# brewpi.net
KiCad netlist of a schematic drawn in EAGLE
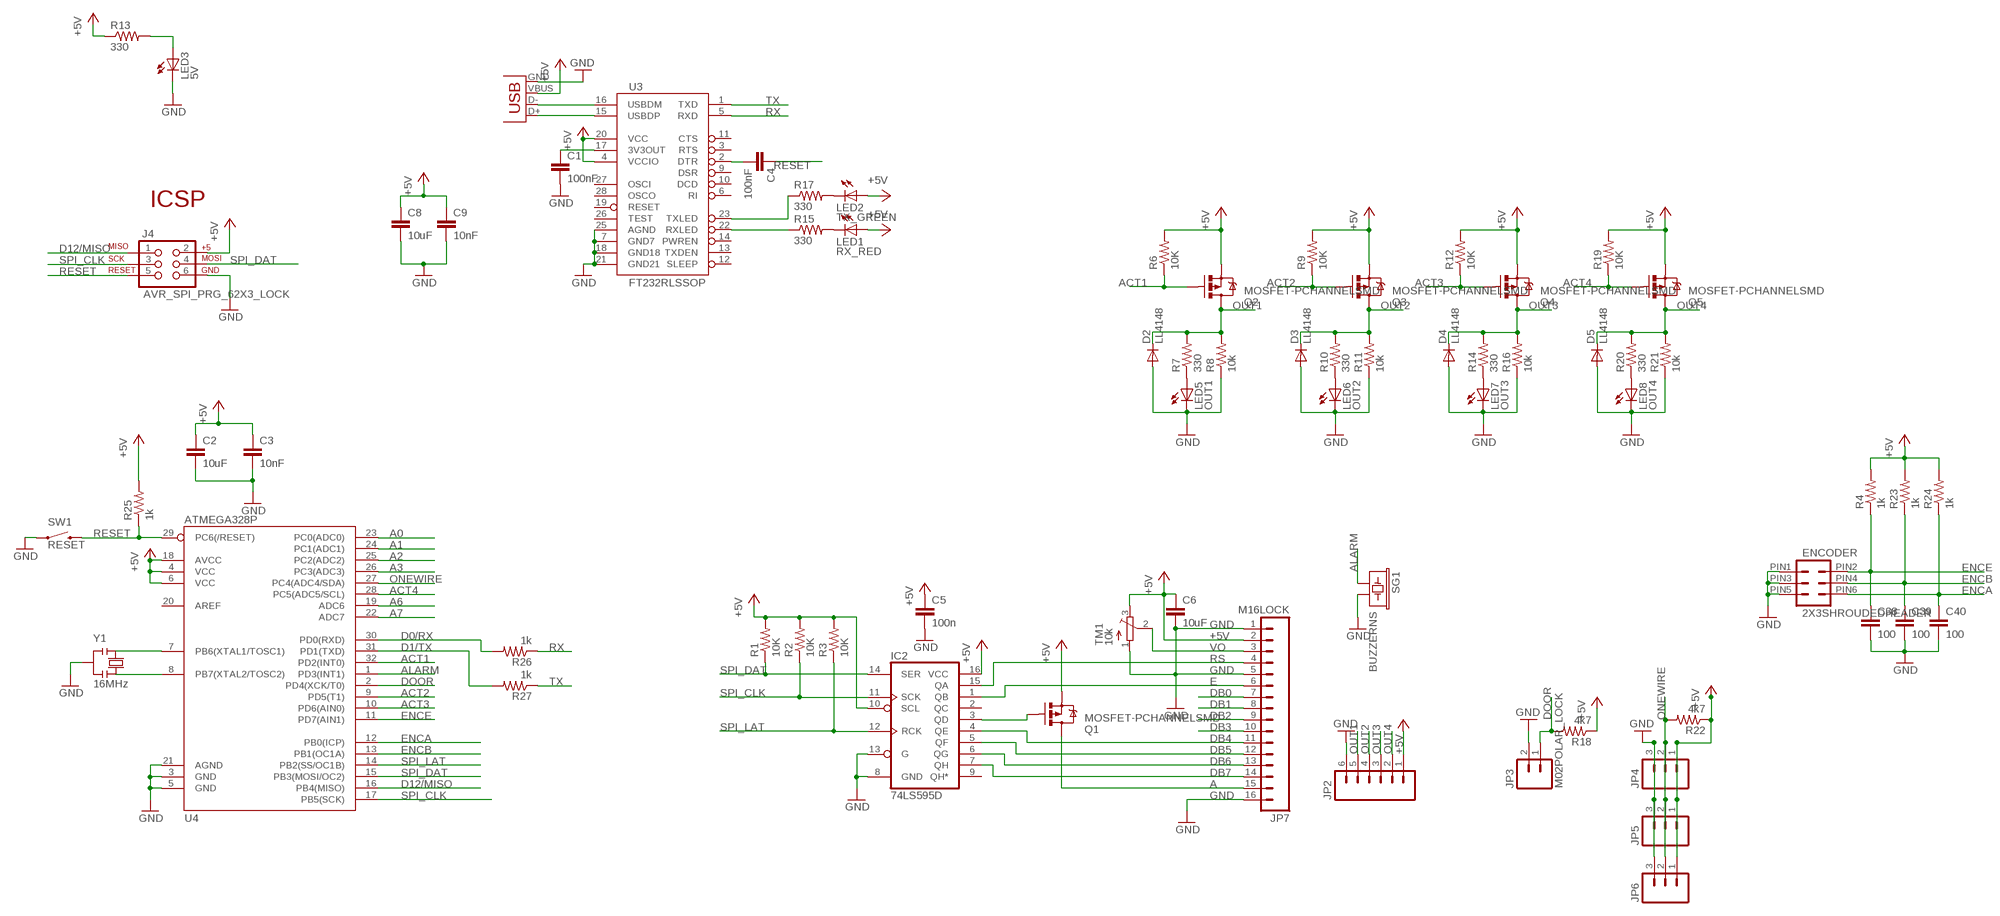
[diagram p0: schematic, sheet 1]

(export (version "E")
  (design (tool "Eeschema 10.0.6"))
  (components
    (comp (ref "C1")
      (value "100nF")
      (footprint "eagle-import:0603-CAP")
      (libsource (lib "eagle-import") (part "SparkFun-Capacitors_CAP0603-CAP"))
    )
    (comp (ref "C2")
      (value "10uF")
      (footprint "eagle-import:0603-CAP")
      (libsource (lib "eagle-import") (part "SparkFun-Capacitors_CAP0603-CAP"))
    )
    (comp (ref "C3")
      (value "10nF")
      (footprint "eagle-import:0603-CAP")
      (libsource (lib "eagle-import") (part "SparkFun-Capacitors_CAP0603-CAP"))
    )
    (comp (ref "C4")
      (value "100nF")
      (footprint "eagle-import:0603-CAP")
      (libsource (lib "eagle-import") (part "SparkFun-Capacitors_CAP0603-CAP"))
    )
    (comp (ref "C5")
      (value "100n")
      (footprint "eagle-import:0603-CAP")
      (libsource (lib "eagle-import") (part "SparkFun-Capacitors_CAP0603-CAP"))
    )
    (comp (ref "C6")
      (value "10uF")
      (footprint "eagle-import:0603-CAP")
      (libsource (lib "eagle-import") (part "SparkFun-Capacitors_CAP0603-CAP"))
    )
    (comp (ref "C8")
      (value "10uF")
      (footprint "eagle-import:0603-CAP")
      (libsource (lib "eagle-import") (part "SparkFun-Capacitors_CAP0603-CAP"))
    )
    (comp (ref "C9")
      (value "10nF")
      (footprint "eagle-import:0603-CAP")
      (libsource (lib "eagle-import") (part "SparkFun-Capacitors_CAP0603-CAP"))
    )
    (comp (ref "C38")
      (value "100")
      (footprint "eagle-import:0603-CAP")
      (libsource (lib "eagle-import") (part "CAP0603-CAP"))
    )
    (comp (ref "C39")
      (value "100")
      (footprint "eagle-import:0603-CAP")
      (libsource (lib "eagle-import") (part "CAP0603-CAP"))
    )
    (comp (ref "C40")
      (value "100")
      (footprint "eagle-import:0603-CAP")
      (libsource (lib "eagle-import") (part "CAP0603-CAP"))
    )
    (comp (ref "D2")
      (value "LL4148")
      (footprint "eagle-import:MLL34")
      (libsource (lib "eagle-import") (part "LL4148"))
    )
    (comp (ref "D3")
      (value "LL4148")
      (footprint "eagle-import:MLL34")
      (libsource (lib "eagle-import") (part "LL4148"))
    )
    (comp (ref "D4")
      (value "LL4148")
      (footprint "eagle-import:MLL34")
      (libsource (lib "eagle-import") (part "LL4148"))
    )
    (comp (ref "D5")
      (value "LL4148")
      (footprint "eagle-import:MLL34")
      (libsource (lib "eagle-import") (part "LL4148"))
    )
    (comp (ref "ENCODER")
      (value "2X3SHROUDEDHEADER")
      (footprint "eagle-import:2X3SHROUDEDHEADER")
      (libsource (lib "eagle-import") (part "2X3SHROUDEDHEADER"))
    )
    (comp (ref "IC2")
      (value "74LS595D")
      (footprint "eagle-import:SO16")
      (libsource (lib "eagle-import") (part "74595DLS"))
    )
    (comp (ref "J4")
      (value "AVR_SPI_PRG_62X3_LOCK")
      (footprint "eagle-import:2X3_LOCK")
      (libsource (lib "eagle-import") (part "AVR_SPI_PRG_62X3_LOCK"))
    )
    (comp (ref "JP1")
      (value "USBSMD")
      (footprint "eagle-import:USB-MINIB")
      (libsource (lib "eagle-import") (part "USBSMD"))
    )
    (comp (ref "JP2")
      (value "M06POLAR_LOCK")
      (footprint "eagle-import:MOLEX-1X6_LOCK")
      (libsource (lib "eagle-import") (part "M06POLAR_LOCK"))
    )
    (comp (ref "JP3")
      (value "M02POLAR_LOCK")
      (footprint "eagle-import:MOLEX-1X2_LOCK")
      (libsource (lib "eagle-import") (part "M02POLAR_LOCK"))
    )
    (comp (ref "JP4")
      (value "M03POLAR_LOCK")
      (footprint "eagle-import:MOLEX-1X3_LOCK")
      (libsource (lib "eagle-import") (part "M03POLAR_LOCK"))
    )
    (comp (ref "JP5")
      (value "M03POLAR_LOCK")
      (footprint "eagle-import:MOLEX-1X3_LOCK")
      (libsource (lib "eagle-import") (part "M03POLAR_LOCK"))
    )
    (comp (ref "JP6")
      (value "M03POLAR_LOCK")
      (footprint "eagle-import:MOLEX-1X3_LOCK")
      (libsource (lib "eagle-import") (part "M03POLAR_LOCK"))
    )
    (comp (ref "JP7")
      (value "M16LOCK")
      (footprint "eagle-import:1X16_LOCK")
      (libsource (lib "eagle-import") (part "M16LOCK"))
    )
    (comp (ref "LED1")
      (value "RX_RED")
      (footprint "eagle-import:LED-0603")
      (libsource (lib "eagle-import") (part "LED0603"))
    )
    (comp (ref "LED2")
      (value "TX_GREEN")
      (footprint "eagle-import:LED-0603")
      (libsource (lib "eagle-import") (part "LED0603"))
    )
    (comp (ref "LED3")
      (value "5V")
      (footprint "eagle-import:LED-0603")
      (libsource (lib "eagle-import") (part "LED0603"))
    )
    (comp (ref "LED5")
      (value "OUT1")
      (footprint "eagle-import:LED-0603")
      (libsource (lib "eagle-import") (part "LED0603"))
    )
    (comp (ref "LED6")
      (value "OUT2")
      (footprint "eagle-import:LED-0603")
      (libsource (lib "eagle-import") (part "LED0603"))
    )
    (comp (ref "LED7")
      (value "OUT3")
      (footprint "eagle-import:LED-0603")
      (libsource (lib "eagle-import") (part "LED0603"))
    )
    (comp (ref "LED8")
      (value "OUT4")
      (footprint "eagle-import:LED-0603")
      (libsource (lib "eagle-import") (part "LED0603"))
    )
    (comp (ref "Q1")
      (value "MOSFET-PCHANNELSMD")
      (footprint "eagle-import:SOT23-3")
      (libsource (lib "eagle-import") (part "MOSFET-PCHANNELSMD"))
    )
    (comp (ref "Q2")
      (value "MOSFET-PCHANNELSMD")
      (footprint "eagle-import:SOT23-3")
      (libsource (lib "eagle-import") (part "MOSFET-PCHANNELSMD"))
    )
    (comp (ref "Q3")
      (value "MOSFET-PCHANNELSMD")
      (footprint "eagle-import:SOT23-3")
      (libsource (lib "eagle-import") (part "MOSFET-PCHANNELSMD"))
    )
    (comp (ref "Q4")
      (value "MOSFET-PCHANNELSMD")
      (footprint "eagle-import:SOT23-3")
      (libsource (lib "eagle-import") (part "MOSFET-PCHANNELSMD"))
    )
    (comp (ref "Q5")
      (value "MOSFET-PCHANNELSMD")
      (footprint "eagle-import:SOT23-3")
      (libsource (lib "eagle-import") (part "MOSFET-PCHANNELSMD"))
    )
    (comp (ref "R1")
      (value "10K")
      (footprint "eagle-import:0603-RES")
      (libsource (lib "eagle-import") (part "RESISTOR0603-RES"))
    )
    (comp (ref "R2")
      (value "10K")
      (footprint "eagle-import:0603-RES")
      (libsource (lib "eagle-import") (part "RESISTOR0603-RES"))
    )
    (comp (ref "R3")
      (value "10K")
      (footprint "eagle-import:0603-RES")
      (libsource (lib "eagle-import") (part "RESISTOR0603-RES"))
    )
    (comp (ref "R4")
      (value "1k")
      (footprint "eagle-import:R0603")
      (libsource (lib "eagle-import") (part "R-US_R0603"))
    )
    (comp (ref "R6")
      (value "10K")
      (footprint "eagle-import:0603-RES")
      (libsource (lib "eagle-import") (part "RESISTOR0603-RES"))
    )
    (comp (ref "R7")
      (value "330")
      (footprint "eagle-import:0603-RES")
      (libsource (lib "eagle-import") (part "RESISTOR0603-RES"))
    )
    (comp (ref "R8")
      (value "10k")
      (footprint "eagle-import:0603-RES")
      (libsource (lib "eagle-import") (part "RESISTOR0603-RES"))
    )
    (comp (ref "R9")
      (value "10K")
      (footprint "eagle-import:0603-RES")
      (libsource (lib "eagle-import") (part "RESISTOR0603-RES"))
    )
    (comp (ref "R10")
      (value "330")
      (footprint "eagle-import:0603-RES")
      (libsource (lib "eagle-import") (part "RESISTOR0603-RES"))
    )
    (comp (ref "R11")
      (value "10k")
      (footprint "eagle-import:0603-RES")
      (libsource (lib "eagle-import") (part "RESISTOR0603-RES"))
    )
    (comp (ref "R12")
      (value "10K")
      (footprint "eagle-import:0603-RES")
      (libsource (lib "eagle-import") (part "RESISTOR0603-RES"))
    )
    (comp (ref "R13")
      (value "330")
      (footprint "eagle-import:0603-RES")
      (libsource (lib "eagle-import") (part "RESISTOR0603"))
    )
    (comp (ref "R14")
      (value "330")
      (footprint "eagle-import:0603-RES")
      (libsource (lib "eagle-import") (part "RESISTOR0603-RES"))
    )
    (comp (ref "R15")
      (value "330")
      (footprint "eagle-import:0603-RES")
      (libsource (lib "eagle-import") (part "RESISTOR0603"))
    )
    (comp (ref "R16")
      (value "10k")
      (footprint "eagle-import:0603-RES")
      (libsource (lib "eagle-import") (part "RESISTOR0603-RES"))
    )
    (comp (ref "R17")
      (value "330")
      (footprint "eagle-import:0603-RES")
      (libsource (lib "eagle-import") (part "RESISTOR0603"))
    )
    (comp (ref "R18")
      (value "4k7")
      (footprint "eagle-import:0603-RES")
      (libsource (lib "eagle-import") (part "RESISTOR0603-RES"))
    )
    (comp (ref "R19")
      (value "10K")
      (footprint "eagle-import:0603-RES")
      (libsource (lib "eagle-import") (part "RESISTOR0603-RES"))
    )
    (comp (ref "R20")
      (value "330")
      (footprint "eagle-import:0603-RES")
      (libsource (lib "eagle-import") (part "RESISTOR0603-RES"))
    )
    (comp (ref "R21")
      (value "10k")
      (footprint "eagle-import:0603-RES")
      (libsource (lib "eagle-import") (part "RESISTOR0603-RES"))
    )
    (comp (ref "R22")
      (value "4k7")
      (footprint "eagle-import:0603-RES")
      (libsource (lib "eagle-import") (part "RESISTOR0603-RES"))
    )
    (comp (ref "R23")
      (value "1k")
      (footprint "eagle-import:R0603")
      (libsource (lib "eagle-import") (part "R-US_R0603"))
    )
    (comp (ref "R24")
      (value "1k")
      (footprint "eagle-import:R0603")
      (libsource (lib "eagle-import") (part "R-US_R0603"))
    )
    (comp (ref "R25")
      (value "1k")
      (footprint "eagle-import:0603-RES")
      (libsource (lib "eagle-import") (part "RESISTOR0603"))
    )
    (comp (ref "R26")
      (value "1k")
      (footprint "eagle-import:0603-RES")
      (libsource (lib "eagle-import") (part "RESISTOR0603"))
    )
    (comp (ref "R27")
      (value "1k")
      (footprint "eagle-import:0603-RES")
      (libsource (lib "eagle-import") (part "RESISTOR0603"))
    )
    (comp (ref "SG1")
      (value "BUZZERNS")
      (footprint "eagle-import:BUZZER-12MM-NS")
      (libsource (lib "eagle-import") (part "BUZZERNS"))
    )
    (comp (ref "SW1")
      (value "RESET")
      (footprint "eagle-import:TACTILE_SWITCH_TALL")
      (libsource (lib "eagle-import") (part "SWITCH-MOMENTARY-2SMD-4"))
    )
    (comp (ref "TM1")
      (value "10k")
      (footprint "eagle-import:TC33X")
      (libsource (lib "eagle-import") (part "TRIMPOTTC33X"))
    )
    (comp (ref "U3")
      (value "FT232RLSSOP")
      (footprint "eagle-import:SSOP28DB")
      (libsource (lib "eagle-import") (part "FT232RLSSOP"))
    )
    (comp (ref "U4")
      (value "ATMEGA328P")
      (footprint "eagle-import:TQFP32-08")
      (libsource (lib "eagle-import") (part "ATMEGA328_SMT"))
    )
    (comp (ref "Y1")
      (value "16MHz")
      (footprint "eagle-import:RESONATOR")
      (libsource (lib "eagle-import") (part "RESONATORMU"))
    )
  )
  (nets
    (net (code "1") (name "+5V") (class "Default")
      (node (ref "C2") (pin "1") (pinfunction "1_1") (pintype "passive"))
      (node (ref "C3") (pin "1") (pinfunction "1_1") (pintype "passive"))
      (node (ref "C5") (pin "1") (pinfunction "1_1") (pintype "passive"))
      (node (ref "C6") (pin "1") (pinfunction "1_1") (pintype "passive"))
      (node (ref "C8") (pin "1") (pinfunction "1_1") (pintype "passive"))
      (node (ref "C9") (pin "1") (pinfunction "1_1") (pintype "passive"))
      (node (ref "IC2") (pin "10") (pinfunction "SCL_10") (pintype "input"))
      (node (ref "IC2") (pin "16") (pinfunction "VCC_16") (pintype "power_in"))
      (node (ref "J4") (pin "2") (pinfunction "2_2") (pintype "passive"))
      (node (ref "JP1") (pin "VBUS") (pinfunction "VBUS_VBUS") (pintype "bidirectional"))
      (node (ref "JP2") (pin "1") (pinfunction "1_1") (pintype "passive"))
      (node (ref "JP4") (pin "1") (pinfunction "1_1") (pintype "passive"))
      (node (ref "JP5") (pin "1") (pinfunction "1_1") (pintype "passive"))
      (node (ref "JP6") (pin "1") (pinfunction "1_1") (pintype "passive"))
      (node (ref "JP7") (pin "2") (pinfunction "2_2") (pintype "passive"))
      (node (ref "LED1") (pin "A") (pinfunction "A_A") (pintype "passive"))
      (node (ref "LED2") (pin "A") (pinfunction "A_A") (pintype "passive"))
      (node (ref "Q1") (pin "2") (pinfunction "S_2") (pintype "passive"))
      (node (ref "Q2") (pin "2") (pinfunction "S_2") (pintype "passive"))
      (node (ref "Q3") (pin "2") (pinfunction "S_2") (pintype "passive"))
      (node (ref "Q4") (pin "2") (pinfunction "S_2") (pintype "passive"))
      (node (ref "Q5") (pin "2") (pinfunction "S_2") (pintype "passive"))
      (node (ref "R1") (pin "2") (pinfunction "2_2") (pintype "passive"))
      (node (ref "R12") (pin "2") (pinfunction "2_2") (pintype "passive"))
      (node (ref "R13") (pin "1") (pinfunction "1_1") (pintype "passive"))
      (node (ref "R18") (pin "1") (pinfunction "1_1") (pintype "passive"))
      (node (ref "R19") (pin "2") (pinfunction "2_2") (pintype "passive"))
      (node (ref "R2") (pin "2") (pinfunction "2_2") (pintype "passive"))
      (node (ref "R22") (pin "1") (pinfunction "1_1") (pintype "passive"))
      (node (ref "R23") (pin "2") (pinfunction "2_2") (pintype "passive"))
      (node (ref "R24") (pin "2") (pinfunction "2_2") (pintype "passive"))
      (node (ref "R25") (pin "2") (pinfunction "2_2") (pintype "passive"))
      (node (ref "R3") (pin "2") (pinfunction "2_2") (pintype "passive"))
      (node (ref "R4") (pin "2") (pinfunction "2_2") (pintype "passive"))
      (node (ref "R6") (pin "2") (pinfunction "2_2") (pintype "passive"))
      (node (ref "R9") (pin "2") (pinfunction "2_2") (pintype "passive"))
      (node (ref "TM1") (pin "3") (pinfunction "E_3") (pintype "passive"))
      (node (ref "U3") (pin "20") (pinfunction "VCC_20") (pintype "power_in"))
      (node (ref "U3") (pin "4") (pinfunction "VCCIO_4") (pintype "power_in"))
      (node (ref "U4") (pin "18") (pinfunction "AVCC_18") (pintype "bidirectional"))
      (node (ref "U4") (pin "4") (pinfunction "VCC_4") (pintype "bidirectional"))
      (node (ref "U4") (pin "6") (pinfunction "VCC_6") (pintype "bidirectional"))
    )
    (net (code "2") (name "/A") (class "Default")
      (node (ref "JP7") (pin "15") (pinfunction "15_15") (pintype "passive"))
      (node (ref "Q1") (pin "3") (pinfunction "D_3") (pintype "passive"))
    )
    (net (code "3") (name "/A0") (class "Default")
      (node (ref "U4") (pin "23") (pinfunction "PC0(ADC0)_23") (pintype "bidirectional"))
    )
    (net (code "4") (name "/A1") (class "Default")
      (node (ref "U4") (pin "24") (pinfunction "PC1(ADC1)_24") (pintype "bidirectional"))
    )
    (net (code "5") (name "/A2") (class "Default")
      (node (ref "U4") (pin "25") (pinfunction "PC2(ADC2)_25") (pintype "bidirectional"))
    )
    (net (code "6") (name "/A3") (class "Default")
      (node (ref "U4") (pin "26") (pinfunction "PC3(ADC3)_26") (pintype "bidirectional"))
    )
    (net (code "7") (name "/A6") (class "Default")
      (node (ref "U4") (pin "19") (pinfunction "ADC6_19") (pintype "bidirectional"))
    )
    (net (code "8") (name "/A7") (class "Default")
      (node (ref "U4") (pin "22") (pinfunction "ADC7_22") (pintype "bidirectional"))
    )
    (net (code "9") (name "/ACT1") (class "Default")
      (node (ref "Q2") (pin "1") (pinfunction "G_1") (pintype "passive"))
      (node (ref "R6") (pin "1") (pinfunction "1_1") (pintype "passive"))
      (node (ref "U4") (pin "32") (pinfunction "PD2(INT0)_32") (pintype "bidirectional"))
    )
    (net (code "10") (name "/ACT2") (class "Default")
      (node (ref "Q3") (pin "1") (pinfunction "G_1") (pintype "passive"))
      (node (ref "R9") (pin "1") (pinfunction "1_1") (pintype "passive"))
      (node (ref "U4") (pin "9") (pinfunction "PD5(T1)_9") (pintype "bidirectional"))
    )
    (net (code "11") (name "/ACT3") (class "Default")
      (node (ref "Q4") (pin "1") (pinfunction "G_1") (pintype "passive"))
      (node (ref "R12") (pin "1") (pinfunction "1_1") (pintype "passive"))
      (node (ref "U4") (pin "10") (pinfunction "PD6(AIN0)_10") (pintype "bidirectional"))
    )
    (net (code "12") (name "/ACT4") (class "Default")
      (node (ref "Q5") (pin "1") (pinfunction "G_1") (pintype "passive"))
      (node (ref "R19") (pin "1") (pinfunction "1_1") (pintype "passive"))
      (node (ref "U4") (pin "28") (pinfunction "PC5(ADC5/SCL)_28") (pintype "bidirectional"))
    )
    (net (code "13") (name "/ALARM") (class "Default")
      (node (ref "SG1") (pin "+") (pinfunction "1_+") (pintype "passive"))
      (node (ref "U4") (pin "1") (pinfunction "PD3(INT1)_1") (pintype "bidirectional"))
    )
    (net (code "14") (name "/D0{slash}RX") (class "Default")
      (node (ref "R26") (pin "2") (pinfunction "2_2") (pintype "passive"))
      (node (ref "U4") (pin "30") (pinfunction "PD0(RXD)_30") (pintype "bidirectional"))
    )
    (net (code "15") (name "/D1{slash}TX") (class "Default")
      (node (ref "R27") (pin "2") (pinfunction "2_2") (pintype "passive"))
      (node (ref "U4") (pin "31") (pinfunction "PD1(TXD)_31") (pintype "bidirectional"))
    )
    (net (code "16") (name "/D12{slash}MISO") (class "Default")
      (node (ref "J4") (pin "1") (pinfunction "1_1") (pintype "passive"))
      (node (ref "U4") (pin "16") (pinfunction "PB4(MISO)_16") (pintype "bidirectional"))
    )
    (net (code "17") (name "/DB0") (class "Default")
      (node (ref "JP7") (pin "7") (pinfunction "7_7") (pintype "passive"))
    )
    (net (code "18") (name "/DB1") (class "Default")
      (node (ref "JP7") (pin "8") (pinfunction "8_8") (pintype "passive"))
    )
    (net (code "19") (name "/DB2") (class "Default")
      (node (ref "JP7") (pin "9") (pinfunction "9_9") (pintype "passive"))
    )
    (net (code "20") (name "/DB3") (class "Default")
      (node (ref "JP7") (pin "10") (pinfunction "10_10") (pintype "passive"))
    )
    (net (code "21") (name "/DB4") (class "Default")
      (node (ref "IC2") (pin "4") (pinfunction "QE_4") (pintype "tri_state"))
      (node (ref "JP7") (pin "11") (pinfunction "11_11") (pintype "passive"))
    )
    (net (code "22") (name "/DB5") (class "Default")
      (node (ref "IC2") (pin "5") (pinfunction "QF_5") (pintype "tri_state"))
      (node (ref "JP7") (pin "12") (pinfunction "12_12") (pintype "passive"))
    )
    (net (code "23") (name "/DB6") (class "Default")
      (node (ref "IC2") (pin "6") (pinfunction "QG_6") (pintype "tri_state"))
      (node (ref "JP7") (pin "13") (pinfunction "13_13") (pintype "passive"))
    )
    (net (code "24") (name "/DB7") (class "Default")
      (node (ref "IC2") (pin "7") (pinfunction "QH_7") (pintype "tri_state"))
      (node (ref "JP7") (pin "14") (pinfunction "14_14") (pintype "passive"))
    )
    (net (code "25") (name "/DOOR") (class "Default")
      (node (ref "JP3") (pin "1") (pinfunction "1_1") (pintype "passive"))
      (node (ref "R18") (pin "2") (pinfunction "2_2") (pintype "passive"))
      (node (ref "U4") (pin "2") (pinfunction "PD4(XCK/T0)_2") (pintype "bidirectional"))
    )
    (net (code "26") (name "/E") (class "Default")
      (node (ref "IC2") (pin "1") (pinfunction "QB_1") (pintype "tri_state"))
      (node (ref "JP7") (pin "6") (pinfunction "6_6") (pintype "passive"))
    )
    (net (code "27") (name "/ENCA") (class "Default")
      (node (ref "C40") (pin "1") (pinfunction "1_1") (pintype "passive"))
      (node (ref "ENCODER") (pin "PIN6") (pinfunction "6_PIN6") (pintype "passive"))
      (node (ref "R24") (pin "1") (pinfunction "1_1") (pintype "passive"))
      (node (ref "U4") (pin "12") (pinfunction "PB0(ICP)_12") (pintype "bidirectional"))
    )
    (net (code "28") (name "/ENCB") (class "Default")
      (node (ref "C39") (pin "1") (pinfunction "1_1") (pintype "passive"))
      (node (ref "ENCODER") (pin "PIN4") (pinfunction "4_PIN4") (pintype "passive"))
      (node (ref "R23") (pin "1") (pinfunction "1_1") (pintype "passive"))
      (node (ref "U4") (pin "13") (pinfunction "PB1(OC1A)_13") (pintype "bidirectional"))
    )
    (net (code "29") (name "/ENCE") (class "Default")
      (node (ref "C38") (pin "1") (pinfunction "1_1") (pintype "passive"))
      (node (ref "ENCODER") (pin "PIN2") (pinfunction "2_PIN2") (pintype "passive"))
      (node (ref "R4") (pin "1") (pinfunction "1_1") (pintype "passive"))
      (node (ref "U4") (pin "11") (pinfunction "PD7(AIN1)_11") (pintype "bidirectional"))
    )
    (net (code "30") (name "/ONEWIRE") (class "Default")
      (node (ref "JP4") (pin "2") (pinfunction "2_2") (pintype "passive"))
      (node (ref "JP5") (pin "2") (pinfunction "2_2") (pintype "passive"))
      (node (ref "JP6") (pin "2") (pinfunction "2_2") (pintype "passive"))
      (node (ref "R22") (pin "2") (pinfunction "2_2") (pintype "passive"))
      (node (ref "U4") (pin "27") (pinfunction "PC4(ADC4/SDA)_27") (pintype "bidirectional"))
    )
    (net (code "31") (name "/OUT1") (class "Default")
      (node (ref "D2") (pin "C") (pinfunction "C_C") (pintype "passive"))
      (node (ref "JP2") (pin "5") (pinfunction "5_5") (pintype "passive"))
      (node (ref "Q2") (pin "3") (pinfunction "D_3") (pintype "passive"))
      (node (ref "R7") (pin "2") (pinfunction "2_2") (pintype "passive"))
      (node (ref "R8") (pin "2") (pinfunction "2_2") (pintype "passive"))
    )
    (net (code "32") (name "/OUT2") (class "Default")
      (node (ref "D3") (pin "C") (pinfunction "C_C") (pintype "passive"))
      (node (ref "JP2") (pin "4") (pinfunction "4_4") (pintype "passive"))
      (node (ref "Q3") (pin "3") (pinfunction "D_3") (pintype "passive"))
      (node (ref "R10") (pin "2") (pinfunction "2_2") (pintype "passive"))
      (node (ref "R11") (pin "2") (pinfunction "2_2") (pintype "passive"))
    )
    (net (code "33") (name "/OUT3") (class "Default")
      (node (ref "D4") (pin "C") (pinfunction "C_C") (pintype "passive"))
      (node (ref "JP2") (pin "3") (pinfunction "3_3") (pintype "passive"))
      (node (ref "Q4") (pin "3") (pinfunction "D_3") (pintype "passive"))
      (node (ref "R14") (pin "2") (pinfunction "2_2") (pintype "passive"))
      (node (ref "R16") (pin "2") (pinfunction "2_2") (pintype "passive"))
    )
    (net (code "34") (name "/OUT4") (class "Default")
      (node (ref "D5") (pin "C") (pinfunction "C_C") (pintype "passive"))
      (node (ref "JP2") (pin "2") (pinfunction "2_2") (pintype "passive"))
      (node (ref "Q5") (pin "3") (pinfunction "D_3") (pintype "passive"))
      (node (ref "R20") (pin "2") (pinfunction "2_2") (pintype "passive"))
      (node (ref "R21") (pin "2") (pinfunction "2_2") (pintype "passive"))
    )
    (net (code "35") (name "/RESET") (class "Default")
      (node (ref "C4") (pin "1") (pinfunction "1_1") (pintype "passive"))
      (node (ref "J4") (pin "5") (pinfunction "5_5") (pintype "passive"))
      (node (ref "R25") (pin "1") (pinfunction "1_1") (pintype "passive"))
      (node (ref "SW1") (pin "B2") (pinfunction "2_B2") (pintype "passive"))
      (node (ref "U4") (pin "29") (pinfunction "PC6(/RESET)_29") (pintype "bidirectional"))
    )
    (net (code "36") (name "/RS") (class "Default")
      (node (ref "IC2") (pin "15") (pinfunction "QA_15") (pintype "tri_state"))
      (node (ref "JP7") (pin "4") (pinfunction "4_4") (pintype "passive"))
    )
    (net (code "37") (name "/RX") (class "Default")
      (node (ref "R26") (pin "1") (pinfunction "1_1") (pintype "passive"))
      (node (ref "U3") (pin "5") (pinfunction "RXD_5") (pintype "input"))
    )
    (net (code "38") (name "/SPI_CLK") (class "Default")
      (node (ref "IC2") (pin "11") (pinfunction "SCK_11") (pintype "input"))
      (node (ref "J4") (pin "3") (pinfunction "3_3") (pintype "passive"))
      (node (ref "R2") (pin "1") (pinfunction "1_1") (pintype "passive"))
      (node (ref "U4") (pin "17") (pinfunction "PB5(SCK)_17") (pintype "bidirectional"))
    )
    (net (code "39") (name "/SPI_DAT") (class "Default")
      (node (ref "IC2") (pin "14") (pinfunction "SER_14") (pintype "input"))
      (node (ref "J4") (pin "4") (pinfunction "4_4") (pintype "passive"))
      (node (ref "R1") (pin "1") (pinfunction "1_1") (pintype "passive"))
      (node (ref "U4") (pin "15") (pinfunction "PB3(MOSI/OC2)_15") (pintype "bidirectional"))
    )
    (net (code "40") (name "/SPI_LAT") (class "Default")
      (node (ref "IC2") (pin "12") (pinfunction "RCK_12") (pintype "input"))
      (node (ref "R3") (pin "1") (pinfunction "1_1") (pintype "passive"))
      (node (ref "U4") (pin "14") (pinfunction "PB2(SS/OC1B)_14") (pintype "bidirectional"))
    )
    (net (code "41") (name "/TX") (class "Default")
      (node (ref "R27") (pin "1") (pinfunction "1_1") (pintype "passive"))
      (node (ref "U3") (pin "1") (pinfunction "TXD_1") (pintype "output"))
    )
    (net (code "42") (name "/VO") (class "Default")
      (node (ref "JP7") (pin "3") (pinfunction "3_3") (pintype "passive"))
      (node (ref "TM1") (pin "2") (pinfunction "S_2") (pintype "passive"))
    )
    (net (code "43") (name "GND") (class "Default")
      (node (ref "C1") (pin "2") (pinfunction "2_2") (pintype "passive"))
      (node (ref "C2") (pin "2") (pinfunction "2_2") (pintype "passive"))
      (node (ref "C3") (pin "2") (pinfunction "2_2") (pintype "passive"))
      (node (ref "C38") (pin "2") (pinfunction "2_2") (pintype "passive"))
      (node (ref "C39") (pin "2") (pinfunction "2_2") (pintype "passive"))
      (node (ref "C40") (pin "2") (pinfunction "2_2") (pintype "passive"))
      (node (ref "C5") (pin "2") (pinfunction "2_2") (pintype "passive"))
      (node (ref "C6") (pin "2") (pinfunction "2_2") (pintype "passive"))
      (node (ref "C8") (pin "2") (pinfunction "2_2") (pintype "passive"))
      (node (ref "C9") (pin "2") (pinfunction "2_2") (pintype "passive"))
      (node (ref "D2") (pin "A") (pinfunction "A_A") (pintype "passive"))
      (node (ref "D3") (pin "A") (pinfunction "A_A") (pintype "passive"))
      (node (ref "D4") (pin "A") (pinfunction "A_A") (pintype "passive"))
      (node (ref "D5") (pin "A") (pinfunction "A_A") (pintype "passive"))
      (node (ref "ENCODER") (pin "PIN1") (pinfunction "1_PIN1") (pintype "passive"))
      (node (ref "ENCODER") (pin "PIN3") (pinfunction "3_PIN3") (pintype "passive"))
      (node (ref "ENCODER") (pin "PIN5") (pinfunction "5_PIN5") (pintype "passive"))
      (node (ref "IC2") (pin "13") (pinfunction "G_13") (pintype "input"))
      (node (ref "IC2") (pin "8") (pinfunction "GND_8") (pintype "power_in"))
      (node (ref "J4") (pin "6") (pinfunction "6_6") (pintype "passive"))
      (node (ref "JP1") (pin "GND") (pinfunction "GND_GND") (pintype "bidirectional"))
      (node (ref "JP2") (pin "6") (pinfunction "6_6") (pintype "passive"))
      (node (ref "JP3") (pin "2") (pinfunction "2_2") (pintype "passive"))
      (node (ref "JP4") (pin "3") (pinfunction "3_3") (pintype "passive"))
      (node (ref "JP5") (pin "3") (pinfunction "3_3") (pintype "passive"))
      (node (ref "JP6") (pin "3") (pinfunction "3_3") (pintype "passive"))
      (node (ref "JP7") (pin "1") (pinfunction "1_1") (pintype "passive"))
      (node (ref "JP7") (pin "16") (pinfunction "16_16") (pintype "passive"))
      (node (ref "JP7") (pin "5") (pinfunction "5_5") (pintype "passive"))
      (node (ref "LED3") (pin "C") (pinfunction "C_C") (pintype "passive"))
      (node (ref "LED5") (pin "C") (pinfunction "C_C") (pintype "passive"))
      (node (ref "LED6") (pin "C") (pinfunction "C_C") (pintype "passive"))
      (node (ref "LED7") (pin "C") (pinfunction "C_C") (pintype "passive"))
      (node (ref "LED8") (pin "C") (pinfunction "C_C") (pintype "passive"))
      (node (ref "R11") (pin "1") (pinfunction "1_1") (pintype "passive"))
      (node (ref "R16") (pin "1") (pinfunction "1_1") (pintype "passive"))
      (node (ref "R21") (pin "1") (pinfunction "1_1") (pintype "passive"))
      (node (ref "R8") (pin "1") (pinfunction "1_1") (pintype "passive"))
      (node (ref "SG1") (pin "-") (pinfunction "2_-") (pintype "passive"))
      (node (ref "SW1") (pin "A2") (pinfunction "1_A2") (pintype "passive"))
      (node (ref "TM1") (pin "1") (pinfunction "A_1") (pintype "passive"))
      (node (ref "U3") (pin "18") (pinfunction "GND18_18") (pintype "power_in"))
      (node (ref "U3") (pin "21") (pinfunction "GND21_21") (pintype "power_in"))
      (node (ref "U3") (pin "25") (pinfunction "AGND_25") (pintype "power_in"))
      (node (ref "U3") (pin "7") (pinfunction "GND7_7") (pintype "power_in"))
      (node (ref "U4") (pin "21") (pinfunction "AGND_21") (pintype "bidirectional"))
      (node (ref "U4") (pin "3") (pinfunction "GND_3") (pintype "bidirectional"))
      (node (ref "U4") (pin "5") (pinfunction "GND_5") (pintype "bidirectional"))
      (node (ref "Y1") (pin "2") (pinfunction "2_2") (pintype "passive"))
    )
    (net (code "44") (name "Net-(IC2-QD)") (class "Default")
      (node (ref "IC2") (pin "3") (pinfunction "QD_3") (pintype "tri_state"))
      (node (ref "Q1") (pin "1") (pinfunction "G_1") (pintype "passive"))
    )
    (net (code "45") (name "Net-(LED1-PadC)") (class "Default")
      (node (ref "LED1") (pin "C") (pinfunction "C_C") (pintype "passive"))
      (node (ref "R15") (pin "2") (pinfunction "2_2") (pintype "passive"))
    )
    (net (code "46") (name "Net-(LED2-PadC)") (class "Default")
      (node (ref "LED2") (pin "C") (pinfunction "C_C") (pintype "passive"))
      (node (ref "R17") (pin "2") (pinfunction "2_2") (pintype "passive"))
    )
    (net (code "47") (name "Net-(LED3-PadA)") (class "Default")
      (node (ref "LED3") (pin "A") (pinfunction "A_A") (pintype "passive"))
      (node (ref "R13") (pin "2") (pinfunction "2_2") (pintype "passive"))
    )
    (net (code "48") (name "Net-(LED5-PadA)") (class "Default")
      (node (ref "LED5") (pin "A") (pinfunction "A_A") (pintype "passive"))
      (node (ref "R7") (pin "1") (pinfunction "1_1") (pintype "passive"))
    )
    (net (code "49") (name "Net-(LED6-PadA)") (class "Default")
      (node (ref "LED6") (pin "A") (pinfunction "A_A") (pintype "passive"))
      (node (ref "R10") (pin "1") (pinfunction "1_1") (pintype "passive"))
    )
    (net (code "50") (name "Net-(LED7-PadA)") (class "Default")
      (node (ref "LED7") (pin "A") (pinfunction "A_A") (pintype "passive"))
      (node (ref "R14") (pin "1") (pinfunction "1_1") (pintype "passive"))
    )
    (net (code "51") (name "Net-(LED8-PadA)") (class "Default")
      (node (ref "LED8") (pin "A") (pinfunction "A_A") (pintype "passive"))
      (node (ref "R20") (pin "1") (pinfunction "1_1") (pintype "passive"))
    )
    (net (code "52") (name "Net-(U3-3V3OUT)") (class "Default")
      (node (ref "C1") (pin "1") (pinfunction "1_1") (pintype "passive"))
      (node (ref "U3") (pin "17") (pinfunction "3V3OUT_17") (pintype "output"))
    )
    (net (code "53") (name "Net-(U3-DTR)") (class "Default")
      (node (ref "C4") (pin "2") (pinfunction "2_2") (pintype "passive"))
      (node (ref "U3") (pin "2") (pinfunction "DTR_2") (pintype "output"))
    )
    (net (code "54") (name "Net-(U3-RXLED)") (class "Default")
      (node (ref "R15") (pin "1") (pinfunction "1_1") (pintype "passive"))
      (node (ref "U3") (pin "22") (pinfunction "RXLED_22") (pintype "input"))
    )
    (net (code "55") (name "Net-(U3-TXLED)") (class "Default")
      (node (ref "R17") (pin "1") (pinfunction "1_1") (pintype "passive"))
      (node (ref "U3") (pin "23") (pinfunction "TXLED_23") (pintype "input"))
    )
    (net (code "56") (name "Net-(U3-USBDM)") (class "Default")
      (node (ref "JP1") (pin "D-") (pinfunction "D-_D-") (pintype "bidirectional"))
      (node (ref "U3") (pin "16") (pinfunction "USBDM_16") (pintype "bidirectional"))
    )
    (net (code "57") (name "Net-(U3-USBDP)") (class "Default")
      (node (ref "JP1") (pin "D+") (pinfunction "D+_D+") (pintype "bidirectional"))
      (node (ref "U3") (pin "15") (pinfunction "USBDP_15") (pintype "bidirectional"))
    )
    (net (code "58") (name "Net-(U4-PB6(XTAL1{slash}TOSC1))") (class "Default")
      (node (ref "U4") (pin "7") (pinfunction "PB6(XTAL1/TOSC1)_7") (pintype "bidirectional"))
      (node (ref "Y1") (pin "1") (pinfunction "1_1") (pintype "passive"))
    )
    (net (code "59") (name "Net-(U4-PB7(XTAL2{slash}TOSC2))") (class "Default")
      (node (ref "U4") (pin "8") (pinfunction "PB7(XTAL2/TOSC2)_8") (pintype "bidirectional"))
      (node (ref "Y1") (pin "3") (pinfunction "3_3") (pintype "passive"))
    )
    (net (code "60") (name "unconnected-(IC2-QC-Pad2)") (class "Default")
      (node (ref "IC2") (pin "2") (pinfunction "QC_2") (pintype "tri_state"))
    )
    (net (code "61") (name "unconnected-(IC2-QH*-Pad9)") (class "Default")
      (node (ref "IC2") (pin "9") (pinfunction "QH*_9") (pintype "tri_state"))
    )
    (net (code "62") (name "unconnected-(U3-CTS-Pad11)") (class "Default")
      (node (ref "U3") (pin "11") (pinfunction "CTS_11") (pintype "input"))
    )
    (net (code "63") (name "unconnected-(U3-DCD-Pad10)") (class "Default")
      (node (ref "U3") (pin "10") (pinfunction "DCD_10") (pintype "input"))
    )
    (net (code "64") (name "unconnected-(U3-DSR-Pad9)") (class "Default")
      (node (ref "U3") (pin "9") (pinfunction "DSR_9") (pintype "input"))
    )
    (net (code "65") (name "unconnected-(U3-OSCI-Pad27)") (class "Default")
      (node (ref "U3") (pin "27") (pinfunction "OSCI_27") (pintype "input"))
    )
    (net (code "66") (name "unconnected-(U3-OSCO-Pad28)") (class "Default")
      (node (ref "U3") (pin "28") (pinfunction "OSCO_28") (pintype "output"))
    )
    (net (code "67") (name "unconnected-(U3-PWREN-Pad14)") (class "Default")
      (node (ref "U3") (pin "14") (pinfunction "PWREN_14") (pintype "input"))
    )
    (net (code "68") (name "unconnected-(U3-RESET-Pad19)") (class "Default")
      (node (ref "U3") (pin "19") (pinfunction "RESET_19") (pintype "input"))
    )
    (net (code "69") (name "unconnected-(U3-RI-Pad6)") (class "Default")
      (node (ref "U3") (pin "6") (pinfunction "RI_6") (pintype "input"))
    )
    (net (code "70") (name "unconnected-(U3-RTS-Pad3)") (class "Default")
      (node (ref "U3") (pin "3") (pinfunction "RTS_3") (pintype "output"))
    )
    (net (code "71") (name "unconnected-(U3-SLEEP-Pad12)") (class "Default")
      (node (ref "U3") (pin "12") (pinfunction "SLEEP_12") (pintype "input"))
    )
    (net (code "72") (name "unconnected-(U3-TEST-Pad26)") (class "Default")
      (node (ref "U3") (pin "26") (pinfunction "TEST_26") (pintype "input"))
    )
    (net (code "73") (name "unconnected-(U3-TXDEN-Pad13)") (class "Default")
      (node (ref "U3") (pin "13") (pinfunction "TXDEN_13") (pintype "input"))
    )
    (net (code "74") (name "unconnected-(U4-AREF-Pad20)") (class "Default")
      (node (ref "U4") (pin "20") (pinfunction "AREF_20") (pintype "bidirectional"))
    )
  )
)
